# dronemonster.net
KiCad netlist of a schematic drawn in EAGLE
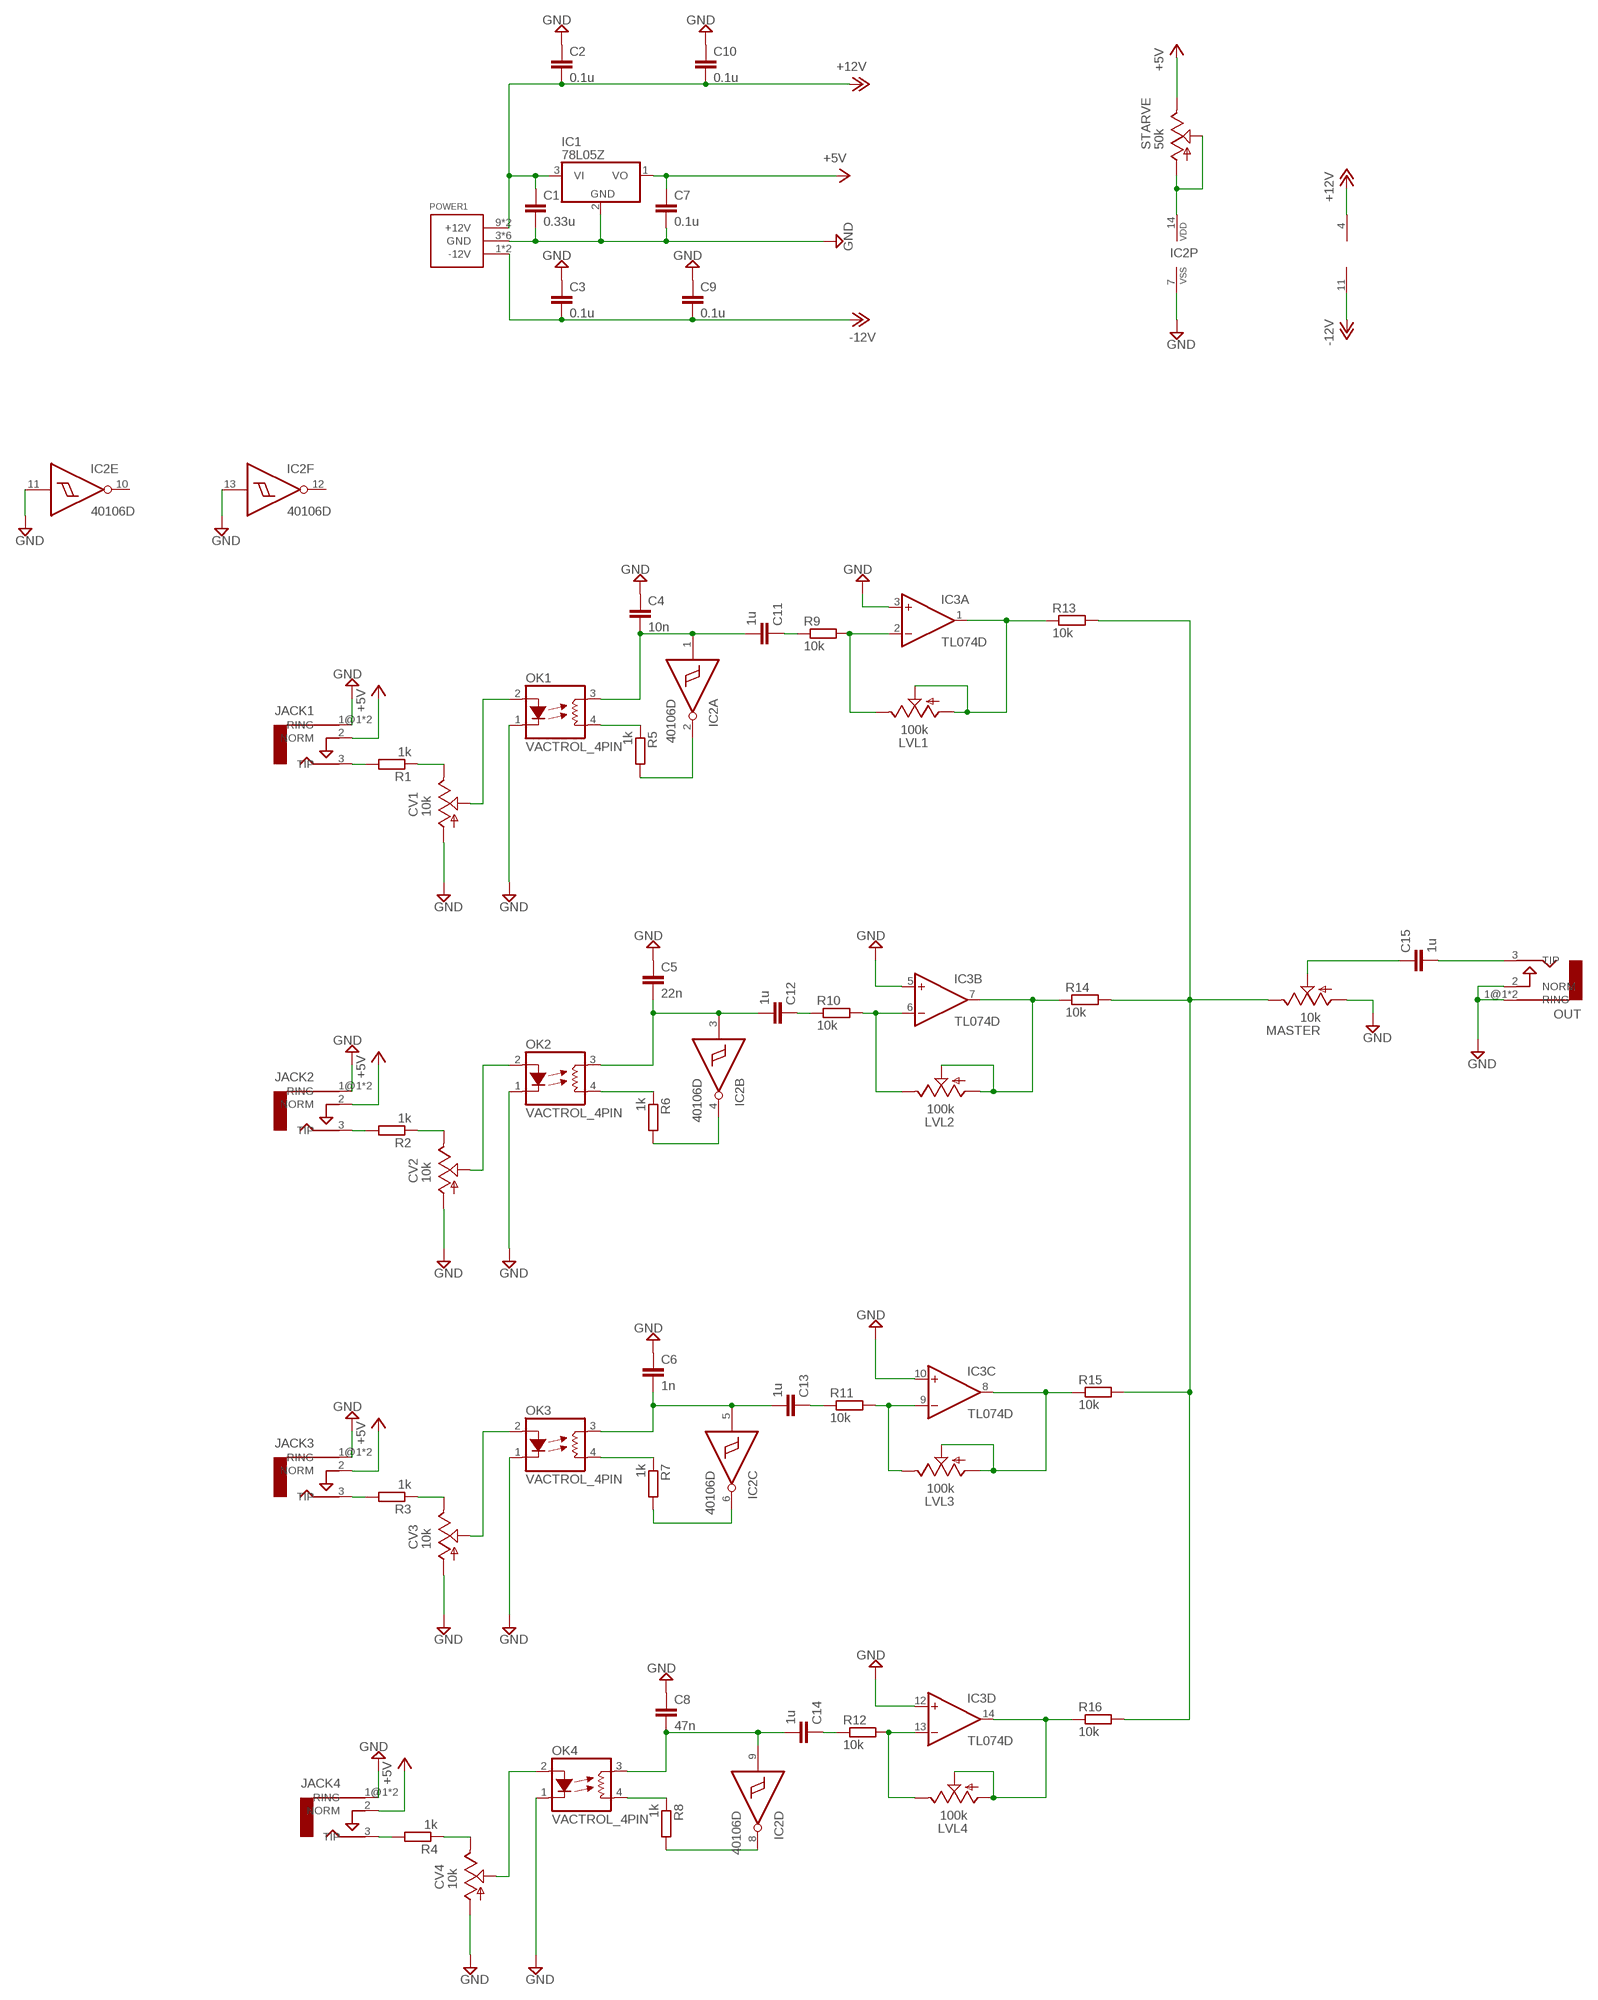
[diagram p0: schematic, sheet 1]

(export (version "E")
  (design (tool "Eeschema 10.0.6"))
  (components
    (comp (ref "C1")
      (value "0.33u")
      (footprint "eagle-import:C0805")
      (libsource (lib "eagle-import") (part "C-EUC0805"))
    )
    (comp (ref "C2")
      (value "0.1u")
      (footprint "eagle-import:C0805")
      (libsource (lib "eagle-import") (part "C-EUC0805"))
    )
    (comp (ref "C3")
      (value "0.1u")
      (footprint "eagle-import:C0805")
      (libsource (lib "eagle-import") (part "C-EUC0805"))
    )
    (comp (ref "C4")
      (value "10n")
      (footprint "eagle-import:C0805")
      (libsource (lib "eagle-import") (part "C-EUC0805"))
    )
    (comp (ref "C5")
      (value "22n")
      (footprint "eagle-import:C0805")
      (libsource (lib "eagle-import") (part "C-EUC0805"))
    )
    (comp (ref "C6")
      (value "1n")
      (footprint "eagle-import:C0805")
      (libsource (lib "eagle-import") (part "C-EUC0805"))
    )
    (comp (ref "C7")
      (value "0.1u")
      (footprint "eagle-import:C0805")
      (libsource (lib "eagle-import") (part "C-EUC0805"))
    )
    (comp (ref "C8")
      (value "47n")
      (footprint "eagle-import:C0805")
      (libsource (lib "eagle-import") (part "C-EUC0805"))
    )
    (comp (ref "C9")
      (value "0.1u")
      (footprint "eagle-import:C0805")
      (libsource (lib "eagle-import") (part "C-EUC0805"))
    )
    (comp (ref "C10")
      (value "0.1u")
      (footprint "eagle-import:C0805")
      (libsource (lib "eagle-import") (part "C-EUC0805"))
    )
    (comp (ref "C11")
      (value "1u")
      (footprint "eagle-import:C0805")
      (libsource (lib "eagle-import") (part "C-EUC0805"))
    )
    (comp (ref "C12")
      (value "1u")
      (footprint "eagle-import:C0805")
      (libsource (lib "eagle-import") (part "C-EUC0805"))
    )
    (comp (ref "C13")
      (value "1u")
      (footprint "eagle-import:C0805")
      (libsource (lib "eagle-import") (part "C-EUC0805"))
    )
    (comp (ref "C14")
      (value "1u")
      (footprint "eagle-import:C0805")
      (libsource (lib "eagle-import") (part "C-EUC0805"))
    )
    (comp (ref "C15")
      (value "1u")
      (footprint "eagle-import:C0805")
      (libsource (lib "eagle-import") (part "C-EUC0805"))
    )
    (comp (ref "CV1")
      (value "10k")
      (footprint "eagle-import:9MM_SNAP-IN_POT")
      (libsource (lib "eagle-import") (part "9MM_SNAP-IN_POT_"))
    )
    (comp (ref "CV2")
      (value "10k")
      (footprint "eagle-import:9MM_SNAP-IN_POT")
      (libsource (lib "eagle-import") (part "9MM_SNAP-IN_POT_"))
    )
    (comp (ref "CV3")
      (value "10k")
      (footprint "eagle-import:9MM_SNAP-IN_POT")
      (libsource (lib "eagle-import") (part "9MM_SNAP-IN_POT_"))
    )
    (comp (ref "CV4")
      (value "10k")
      (footprint "eagle-import:9MM_SNAP-IN_POT")
      (libsource (lib "eagle-import") (part "9MM_SNAP-IN_POT_"))
    )
    (comp (ref "IC1")
      (value "78L05Z")
      (footprint "eagle-import:TO92")
      (libsource (lib "eagle-import") (part "78ZL05"))
    )
    (comp (ref "IC2")
      (value "40106D")
      (footprint "eagle-import:SO14")
      (libsource (lib "eagle-import") (part "40106D"))
    )
    (comp (ref "IC3")
      (value "TL074D")
      (footprint "eagle-import:SO14")
      (libsource (lib "eagle-import") (part "TL074D"))
    )
    (comp (ref "JACK1")
      (value "IN1")
      (footprint "eagle-import:ERTHENVAR-JACK")
      (libsource (lib "eagle-import") (part "AUDIO-JACKERTHENVAR"))
    )
    (comp (ref "JACK2")
      (value "IN2")
      (footprint "eagle-import:ERTHENVAR-JACK")
      (libsource (lib "eagle-import") (part "AUDIO-JACKERTHENVAR"))
    )
    (comp (ref "JACK3")
      (value "IN3")
      (footprint "eagle-import:ERTHENVAR-JACK")
      (libsource (lib "eagle-import") (part "AUDIO-JACKERTHENVAR"))
    )
    (comp (ref "JACK4")
      (value "IN4")
      (footprint "eagle-import:ERTHENVAR-JACK")
      (libsource (lib "eagle-import") (part "AUDIO-JACKERTHENVAR"))
    )
    (comp (ref "LVL1")
      (value "100k")
      (footprint "eagle-import:9MM_SNAP-IN_POT")
      (libsource (lib "eagle-import") (part "9MM_SNAP-IN_POT_"))
    )
    (comp (ref "LVL2")
      (value "100k")
      (footprint "eagle-import:9MM_SNAP-IN_POT")
      (libsource (lib "eagle-import") (part "9MM_SNAP-IN_POT_"))
    )
    (comp (ref "LVL3")
      (value "100k")
      (footprint "eagle-import:9MM_SNAP-IN_POT")
      (libsource (lib "eagle-import") (part "9MM_SNAP-IN_POT_"))
    )
    (comp (ref "LVL4")
      (value "100k")
      (footprint "eagle-import:9MM_SNAP-IN_POT")
      (libsource (lib "eagle-import") (part "9MM_SNAP-IN_POT_"))
    )
    (comp (ref "MASTER")
      (value "10k")
      (footprint "eagle-import:9MM_SNAP-IN_POT")
      (libsource (lib "eagle-import") (part "9MM_SNAP-IN_POT_"))
    )
    (comp (ref "OK1")
      (value "VACTROL_4PIN")
      (footprint "eagle-import:VACTROL_4PIN_VTL5C")
      (libsource (lib "eagle-import") (part "VACTROL_4PIN"))
    )
    (comp (ref "OK2")
      (value "VACTROL_4PIN")
      (footprint "eagle-import:VACTROL_4PIN_VTL5C")
      (libsource (lib "eagle-import") (part "VACTROL_4PIN"))
    )
    (comp (ref "OK3")
      (value "VACTROL_4PIN")
      (footprint "eagle-import:VACTROL_4PIN_VTL5C")
      (libsource (lib "eagle-import") (part "VACTROL_4PIN"))
    )
    (comp (ref "OK4")
      (value "VACTROL_4PIN")
      (footprint "eagle-import:VACTROL_4PIN_VTL5C")
      (libsource (lib "eagle-import") (part "VACTROL_4PIN"))
    )
    (comp (ref "OUT")
      (value "OUT")
      (footprint "eagle-import:ERTHENVAR-JACK")
      (libsource (lib "eagle-import") (part "AUDIO-JACKERTHENVAR"))
    )
    (comp (ref "POWER1")
      (value "POWER_SIMPLE10")
      (footprint "eagle-import:POWER_10")
      (libsource (lib "eagle-import") (part "POWER_SIMPLE10"))
    )
    (comp (ref "R1")
      (value "1k")
      (footprint "eagle-import:R0805")
      (libsource (lib "eagle-import") (part "R-EU_R0805"))
    )
    (comp (ref "R2")
      (value "1k")
      (footprint "eagle-import:R0805")
      (libsource (lib "eagle-import") (part "R-EU_R0805"))
    )
    (comp (ref "R3")
      (value "1k")
      (footprint "eagle-import:R0805")
      (libsource (lib "eagle-import") (part "R-EU_R0805"))
    )
    (comp (ref "R4")
      (value "1k")
      (footprint "eagle-import:R0805")
      (libsource (lib "eagle-import") (part "R-EU_R0805"))
    )
    (comp (ref "R5")
      (value "1k")
      (footprint "eagle-import:R0805")
      (libsource (lib "eagle-import") (part "R-EU_R0805"))
    )
    (comp (ref "R6")
      (value "1k")
      (footprint "eagle-import:R0805")
      (libsource (lib "eagle-import") (part "R-EU_R0805"))
    )
    (comp (ref "R7")
      (value "1k")
      (footprint "eagle-import:R0805")
      (libsource (lib "eagle-import") (part "R-EU_R0805"))
    )
    (comp (ref "R8")
      (value "1k")
      (footprint "eagle-import:R0805")
      (libsource (lib "eagle-import") (part "R-EU_R0805"))
    )
    (comp (ref "R9")
      (value "10k")
      (footprint "eagle-import:R0805")
      (libsource (lib "eagle-import") (part "R-EU_R0805"))
    )
    (comp (ref "R10")
      (value "10k")
      (footprint "eagle-import:R0805")
      (libsource (lib "eagle-import") (part "R-EU_R0805"))
    )
    (comp (ref "R11")
      (value "10k")
      (footprint "eagle-import:R0805")
      (libsource (lib "eagle-import") (part "R-EU_R0805"))
    )
    (comp (ref "R12")
      (value "10k")
      (footprint "eagle-import:R0805")
      (libsource (lib "eagle-import") (part "R-EU_R0805"))
    )
    (comp (ref "R13")
      (value "10k")
      (footprint "eagle-import:R0805")
      (libsource (lib "eagle-import") (part "R-EU_R0805"))
    )
    (comp (ref "R14")
      (value "10k")
      (footprint "eagle-import:R0805")
      (libsource (lib "eagle-import") (part "R-EU_R0805"))
    )
    (comp (ref "R15")
      (value "10k")
      (footprint "eagle-import:R0805")
      (libsource (lib "eagle-import") (part "R-EU_R0805"))
    )
    (comp (ref "R16")
      (value "10k")
      (footprint "eagle-import:R0805")
      (libsource (lib "eagle-import") (part "R-EU_R0805"))
    )
    (comp (ref "STARVE")
      (value "50k")
      (footprint "eagle-import:9MM_SNAP-IN_POT")
      (libsource (lib "eagle-import") (part "9MM_SNAP-IN_POT_"))
    )
  )
  (nets
    (net (code "1") (name "+5V") (class "Default")
      (node (ref "C7") (pin "1") (pinfunction "1_1") (pintype "passive"))
      (node (ref "IC1") (pin "1") (pinfunction "VO_1") (pintype "passive"))
      (node (ref "JACK1") (pin "2") (pinfunction "NORM_2") (pintype "bidirectional"))
      (node (ref "JACK2") (pin "2") (pinfunction "NORM_2") (pintype "bidirectional"))
      (node (ref "JACK3") (pin "2") (pinfunction "NORM_2") (pintype "bidirectional"))
      (node (ref "JACK4") (pin "2") (pinfunction "NORM_2") (pintype "bidirectional"))
      (node (ref "STARVE") (pin "3") (pinfunction "E_3") (pintype "passive"))
    )
    (net (code "2") (name "+12V") (class "Default")
      (node (ref "C1") (pin "1") (pinfunction "1_1") (pintype "passive"))
      (node (ref "C10") (pin "2") (pinfunction "2_2") (pintype "passive"))
      (node (ref "C2") (pin "2") (pinfunction "2_2") (pintype "passive"))
      (node (ref "IC1") (pin "3") (pinfunction "VI_3") (pintype "input"))
      (node (ref "IC3") (pin "4") (pinfunction "V+_4") (pintype "power_in"))
      (node (ref "POWER1") (pin "10") (pinfunction "+12V_10") (pintype "bidirectional"))
      (node (ref "POWER1") (pin "9") (pinfunction "+12V_9") (pintype "bidirectional"))
    )
    (net (code "3") (name "-12V") (class "Default")
      (node (ref "C3") (pin "2") (pinfunction "2_2") (pintype "passive"))
      (node (ref "C9") (pin "2") (pinfunction "2_2") (pintype "passive"))
      (node (ref "IC3") (pin "11") (pinfunction "V-_11") (pintype "power_in"))
      (node (ref "POWER1") (pin "1") (pinfunction "-12V_1") (pintype "bidirectional"))
      (node (ref "POWER1") (pin "2") (pinfunction "-12V_2") (pintype "bidirectional"))
    )
    (net (code "4") (name "GND") (class "Default")
      (node (ref "C1") (pin "2") (pinfunction "2_2") (pintype "passive"))
      (node (ref "C10") (pin "1") (pinfunction "1_1") (pintype "passive"))
      (node (ref "C2") (pin "1") (pinfunction "1_1") (pintype "passive"))
      (node (ref "C3") (pin "1") (pinfunction "1_1") (pintype "passive"))
      (node (ref "C4") (pin "1") (pinfunction "1_1") (pintype "passive"))
      (node (ref "C5") (pin "1") (pinfunction "1_1") (pintype "passive"))
      (node (ref "C6") (pin "1") (pinfunction "1_1") (pintype "passive"))
      (node (ref "C7") (pin "2") (pinfunction "2_2") (pintype "passive"))
      (node (ref "C8") (pin "1") (pinfunction "1_1") (pintype "passive"))
      (node (ref "C9") (pin "1") (pinfunction "1_1") (pintype "passive"))
      (node (ref "CV1") (pin "1") (pinfunction "A_1") (pintype "passive"))
      (node (ref "CV2") (pin "1") (pinfunction "A_1") (pintype "passive"))
      (node (ref "CV3") (pin "1") (pinfunction "A_1") (pintype "passive"))
      (node (ref "CV4") (pin "1") (pinfunction "A_1") (pintype "passive"))
      (node (ref "IC1") (pin "2") (pinfunction "GND_2") (pintype "passive"))
      (node (ref "IC2") (pin "11") (pinfunction "I_11") (pintype "input"))
      (node (ref "IC2") (pin "13") (pinfunction "I_13") (pintype "input"))
      (node (ref "IC2") (pin "7") (pinfunction "VSS_7") (pintype "power_in"))
      (node (ref "IC3") (pin "10") (pinfunction "+IN_10") (pintype "input"))
      (node (ref "IC3") (pin "12") (pinfunction "+IN_12") (pintype "input"))
      (node (ref "IC3") (pin "3") (pinfunction "+IN_3") (pintype "input"))
      (node (ref "IC3") (pin "5") (pinfunction "+IN_5") (pintype "input"))
      (node (ref "JACK1") (pin "1@1") (pinfunction "RING_1@1") (pintype "bidirectional"))
      (node (ref "JACK1") (pin "1@2") (pinfunction "RING_1@2") (pintype "bidirectional"))
      (node (ref "JACK2") (pin "1@1") (pinfunction "RING_1@1") (pintype "bidirectional"))
      (node (ref "JACK2") (pin "1@2") (pinfunction "RING_1@2") (pintype "bidirectional"))
      (node (ref "JACK3") (pin "1@1") (pinfunction "RING_1@1") (pintype "bidirectional"))
      (node (ref "JACK3") (pin "1@2") (pinfunction "RING_1@2") (pintype "bidirectional"))
      (node (ref "JACK4") (pin "1@1") (pinfunction "RING_1@1") (pintype "bidirectional"))
      (node (ref "JACK4") (pin "1@2") (pinfunction "RING_1@2") (pintype "bidirectional"))
      (node (ref "MASTER") (pin "1") (pinfunction "A_1") (pintype "passive"))
      (node (ref "OK1") (pin "1") (pinfunction "LED-_1") (pintype "passive"))
      (node (ref "OK2") (pin "1") (pinfunction "LED-_1") (pintype "passive"))
      (node (ref "OK3") (pin "1") (pinfunction "LED-_1") (pintype "passive"))
      (node (ref "OK4") (pin "1") (pinfunction "LED-_1") (pintype "passive"))
      (node (ref "OUT") (pin "1@1") (pinfunction "RING_1@1") (pintype "bidirectional"))
      (node (ref "OUT") (pin "1@2") (pinfunction "RING_1@2") (pintype "bidirectional"))
      (node (ref "OUT") (pin "2") (pinfunction "NORM_2") (pintype "bidirectional"))
      (node (ref "POWER1") (pin "3") (pinfunction "GND_3") (pintype "bidirectional"))
      (node (ref "POWER1") (pin "4") (pinfunction "GND_4") (pintype "bidirectional"))
      (node (ref "POWER1") (pin "5") (pinfunction "GND_5") (pintype "bidirectional"))
      (node (ref "POWER1") (pin "6") (pinfunction "GND_6") (pintype "bidirectional"))
      (node (ref "POWER1") (pin "7") (pinfunction "GND_7") (pintype "bidirectional"))
      (node (ref "POWER1") (pin "8") (pinfunction "GND_8") (pintype "bidirectional"))
    )
    (net (code "5") (name "Net-(C11-Pad1)") (class "Default")
      (node (ref "C11") (pin "1") (pinfunction "1_1") (pintype "passive"))
      (node (ref "R9") (pin "1") (pinfunction "1_1") (pintype "passive"))
    )
    (net (code "6") (name "Net-(C12-Pad1)") (class "Default")
      (node (ref "C12") (pin "1") (pinfunction "1_1") (pintype "passive"))
      (node (ref "R10") (pin "1") (pinfunction "1_1") (pintype "passive"))
    )
    (net (code "7") (name "Net-(C13-Pad1)") (class "Default")
      (node (ref "C13") (pin "1") (pinfunction "1_1") (pintype "passive"))
      (node (ref "R11") (pin "1") (pinfunction "1_1") (pintype "passive"))
    )
    (net (code "8") (name "Net-(C14-Pad1)") (class "Default")
      (node (ref "C14") (pin "1") (pinfunction "1_1") (pintype "passive"))
      (node (ref "R12") (pin "1") (pinfunction "1_1") (pintype "passive"))
    )
    (net (code "9") (name "Net-(CV1-E)") (class "Default")
      (node (ref "CV1") (pin "3") (pinfunction "E_3") (pintype "passive"))
      (node (ref "R1") (pin "1") (pinfunction "1_1") (pintype "passive"))
    )
    (net (code "10") (name "Net-(CV1-S)") (class "Default")
      (node (ref "CV1") (pin "2") (pinfunction "S_2") (pintype "passive"))
      (node (ref "OK1") (pin "2") (pinfunction "LED+_2") (pintype "passive"))
    )
    (net (code "11") (name "Net-(CV2-E)") (class "Default")
      (node (ref "CV2") (pin "3") (pinfunction "E_3") (pintype "passive"))
      (node (ref "R2") (pin "1") (pinfunction "1_1") (pintype "passive"))
    )
    (net (code "12") (name "Net-(CV2-S)") (class "Default")
      (node (ref "CV2") (pin "2") (pinfunction "S_2") (pintype "passive"))
      (node (ref "OK2") (pin "2") (pinfunction "LED+_2") (pintype "passive"))
    )
    (net (code "13") (name "Net-(CV3-E)") (class "Default")
      (node (ref "CV3") (pin "3") (pinfunction "E_3") (pintype "passive"))
      (node (ref "R3") (pin "1") (pinfunction "1_1") (pintype "passive"))
    )
    (net (code "14") (name "Net-(CV3-S)") (class "Default")
      (node (ref "CV3") (pin "2") (pinfunction "S_2") (pintype "passive"))
      (node (ref "OK3") (pin "2") (pinfunction "LED+_2") (pintype "passive"))
    )
    (net (code "15") (name "Net-(CV4-E)") (class "Default")
      (node (ref "CV4") (pin "3") (pinfunction "E_3") (pintype "passive"))
      (node (ref "R4") (pin "1") (pinfunction "1_1") (pintype "passive"))
    )
    (net (code "16") (name "Net-(CV4-S)") (class "Default")
      (node (ref "CV4") (pin "2") (pinfunction "S_2") (pintype "passive"))
      (node (ref "OK4") (pin "2") (pinfunction "LED+_2") (pintype "passive"))
    )
    (net (code "17") (name "Net-(IC2A-I)") (class "Default")
      (node (ref "C11") (pin "2") (pinfunction "2_2") (pintype "passive"))
      (node (ref "C4") (pin "2") (pinfunction "2_2") (pintype "passive"))
      (node (ref "IC2") (pin "1") (pinfunction "I_1") (pintype "input"))
      (node (ref "OK1") (pin "3") (pinfunction "RES1_3") (pintype "passive"))
    )
    (net (code "18") (name "Net-(IC2A-O)") (class "Default")
      (node (ref "IC2") (pin "2") (pinfunction "O_2") (pintype "output"))
      (node (ref "R5") (pin "2") (pinfunction "2_2") (pintype "passive"))
    )
    (net (code "19") (name "Net-(IC2B-I)") (class "Default")
      (node (ref "C12") (pin "2") (pinfunction "2_2") (pintype "passive"))
      (node (ref "C5") (pin "2") (pinfunction "2_2") (pintype "passive"))
      (node (ref "IC2") (pin "3") (pinfunction "I_3") (pintype "input"))
      (node (ref "OK2") (pin "3") (pinfunction "RES1_3") (pintype "passive"))
    )
    (net (code "20") (name "Net-(IC2B-O)") (class "Default")
      (node (ref "IC2") (pin "4") (pinfunction "O_4") (pintype "output"))
      (node (ref "R6") (pin "2") (pinfunction "2_2") (pintype "passive"))
    )
    (net (code "21") (name "Net-(IC2C-I)") (class "Default")
      (node (ref "C13") (pin "2") (pinfunction "2_2") (pintype "passive"))
      (node (ref "C6") (pin "2") (pinfunction "2_2") (pintype "passive"))
      (node (ref "IC2") (pin "5") (pinfunction "I_5") (pintype "input"))
      (node (ref "OK3") (pin "3") (pinfunction "RES1_3") (pintype "passive"))
    )
    (net (code "22") (name "Net-(IC2C-O)") (class "Default")
      (node (ref "IC2") (pin "6") (pinfunction "O_6") (pintype "output"))
      (node (ref "R7") (pin "2") (pinfunction "2_2") (pintype "passive"))
    )
    (net (code "23") (name "Net-(IC2D-I)") (class "Default")
      (node (ref "C14") (pin "2") (pinfunction "2_2") (pintype "passive"))
      (node (ref "C8") (pin "2") (pinfunction "2_2") (pintype "passive"))
      (node (ref "IC2") (pin "9") (pinfunction "I_9") (pintype "input"))
      (node (ref "OK4") (pin "3") (pinfunction "RES1_3") (pintype "passive"))
    )
    (net (code "24") (name "Net-(IC2D-O)") (class "Default")
      (node (ref "IC2") (pin "8") (pinfunction "O_8") (pintype "output"))
      (node (ref "R8") (pin "2") (pinfunction "2_2") (pintype "passive"))
    )
    (net (code "25") (name "Net-(IC2G-VDD)") (class "Default")
      (node (ref "IC2") (pin "14") (pinfunction "VDD_14") (pintype "power_in"))
      (node (ref "STARVE") (pin "1") (pinfunction "A_1") (pintype "passive"))
      (node (ref "STARVE") (pin "2") (pinfunction "S_2") (pintype "passive"))
    )
    (net (code "26") (name "Net-(IC3A--IN)") (class "Default")
      (node (ref "IC3") (pin "2") (pinfunction "-IN_2") (pintype "input"))
      (node (ref "LVL1") (pin "3") (pinfunction "E_3") (pintype "passive"))
      (node (ref "R9") (pin "2") (pinfunction "2_2") (pintype "passive"))
    )
    (net (code "27") (name "Net-(IC3A-OUT)") (class "Default")
      (node (ref "IC3") (pin "1") (pinfunction "OUT_1") (pintype "output"))
      (node (ref "LVL1") (pin "1") (pinfunction "A_1") (pintype "passive"))
      (node (ref "LVL1") (pin "2") (pinfunction "S_2") (pintype "passive"))
      (node (ref "R13") (pin "1") (pinfunction "1_1") (pintype "passive"))
    )
    (net (code "28") (name "Net-(IC3B--IN)") (class "Default")
      (node (ref "IC3") (pin "6") (pinfunction "-IN_6") (pintype "input"))
      (node (ref "LVL2") (pin "3") (pinfunction "E_3") (pintype "passive"))
      (node (ref "R10") (pin "2") (pinfunction "2_2") (pintype "passive"))
    )
    (net (code "29") (name "Net-(IC3B-OUT)") (class "Default")
      (node (ref "IC3") (pin "7") (pinfunction "OUT_7") (pintype "output"))
      (node (ref "LVL2") (pin "1") (pinfunction "A_1") (pintype "passive"))
      (node (ref "LVL2") (pin "2") (pinfunction "S_2") (pintype "passive"))
      (node (ref "R14") (pin "1") (pinfunction "1_1") (pintype "passive"))
    )
    (net (code "30") (name "Net-(IC3C--IN)") (class "Default")
      (node (ref "IC3") (pin "9") (pinfunction "-IN_9") (pintype "input"))
      (node (ref "LVL3") (pin "3") (pinfunction "E_3") (pintype "passive"))
      (node (ref "R11") (pin "2") (pinfunction "2_2") (pintype "passive"))
    )
    (net (code "31") (name "Net-(IC3C-OUT)") (class "Default")
      (node (ref "IC3") (pin "8") (pinfunction "OUT_8") (pintype "output"))
      (node (ref "LVL3") (pin "1") (pinfunction "A_1") (pintype "passive"))
      (node (ref "LVL3") (pin "2") (pinfunction "S_2") (pintype "passive"))
      (node (ref "R15") (pin "1") (pinfunction "1_1") (pintype "passive"))
    )
    (net (code "32") (name "Net-(IC3D--IN)") (class "Default")
      (node (ref "IC3") (pin "13") (pinfunction "-IN_13") (pintype "input"))
      (node (ref "LVL4") (pin "3") (pinfunction "E_3") (pintype "passive"))
      (node (ref "R12") (pin "2") (pinfunction "2_2") (pintype "passive"))
    )
    (net (code "33") (name "Net-(IC3D-OUT)") (class "Default")
      (node (ref "IC3") (pin "14") (pinfunction "OUT_14") (pintype "output"))
      (node (ref "LVL4") (pin "1") (pinfunction "A_1") (pintype "passive"))
      (node (ref "LVL4") (pin "2") (pinfunction "S_2") (pintype "passive"))
      (node (ref "R16") (pin "1") (pinfunction "1_1") (pintype "passive"))
    )
    (net (code "34") (name "Net-(JACK1-TIP)") (class "Default")
      (node (ref "JACK1") (pin "3") (pinfunction "TIP_3") (pintype "bidirectional"))
      (node (ref "R1") (pin "2") (pinfunction "2_2") (pintype "passive"))
    )
    (net (code "35") (name "Net-(JACK2-TIP)") (class "Default")
      (node (ref "JACK2") (pin "3") (pinfunction "TIP_3") (pintype "bidirectional"))
      (node (ref "R2") (pin "2") (pinfunction "2_2") (pintype "passive"))
    )
    (net (code "36") (name "Net-(JACK3-TIP)") (class "Default")
      (node (ref "JACK3") (pin "3") (pinfunction "TIP_3") (pintype "bidirectional"))
      (node (ref "R3") (pin "2") (pinfunction "2_2") (pintype "passive"))
    )
    (net (code "37") (name "Net-(JACK4-TIP)") (class "Default")
      (node (ref "JACK4") (pin "3") (pinfunction "TIP_3") (pintype "bidirectional"))
      (node (ref "R4") (pin "2") (pinfunction "2_2") (pintype "passive"))
    )
    (net (code "38") (name "Net-(MASTER-E)") (class "Default")
      (node (ref "MASTER") (pin "3") (pinfunction "E_3") (pintype "passive"))
      (node (ref "R13") (pin "2") (pinfunction "2_2") (pintype "passive"))
      (node (ref "R14") (pin "2") (pinfunction "2_2") (pintype "passive"))
      (node (ref "R15") (pin "2") (pinfunction "2_2") (pintype "passive"))
      (node (ref "R16") (pin "2") (pinfunction "2_2") (pintype "passive"))
    )
    (net (code "39") (name "Net-(MASTER-S)") (class "Default")
      (node (ref "C15") (pin "1") (pinfunction "1_1") (pintype "passive"))
      (node (ref "MASTER") (pin "2") (pinfunction "S_2") (pintype "passive"))
    )
    (net (code "40") (name "Net-(OK1-RES2)") (class "Default")
      (node (ref "OK1") (pin "4") (pinfunction "RES2_4") (pintype "passive"))
      (node (ref "R5") (pin "1") (pinfunction "1_1") (pintype "passive"))
    )
    (net (code "41") (name "Net-(OK2-RES2)") (class "Default")
      (node (ref "OK2") (pin "4") (pinfunction "RES2_4") (pintype "passive"))
      (node (ref "R6") (pin "1") (pinfunction "1_1") (pintype "passive"))
    )
    (net (code "42") (name "Net-(OK3-RES2)") (class "Default")
      (node (ref "OK3") (pin "4") (pinfunction "RES2_4") (pintype "passive"))
      (node (ref "R7") (pin "1") (pinfunction "1_1") (pintype "passive"))
    )
    (net (code "43") (name "Net-(OK4-RES2)") (class "Default")
      (node (ref "OK4") (pin "4") (pinfunction "RES2_4") (pintype "passive"))
      (node (ref "R8") (pin "1") (pinfunction "1_1") (pintype "passive"))
    )
    (net (code "44") (name "Net-(OUT-TIP)") (class "Default")
      (node (ref "C15") (pin "2") (pinfunction "2_2") (pintype "passive"))
      (node (ref "OUT") (pin "3") (pinfunction "TIP_3") (pintype "bidirectional"))
    )
    (net (code "45") (name "unconnected-(IC2E-O-Pad10)") (class "Default")
      (node (ref "IC2") (pin "10") (pinfunction "O_10") (pintype "output"))
    )
    (net (code "46") (name "unconnected-(IC2F-O-Pad12)") (class "Default")
      (node (ref "IC2") (pin "12") (pinfunction "O_12") (pintype "output"))
    )
  )
)
